# gyro.net
KiCad netlist of a schematic drawn in Altium Designer
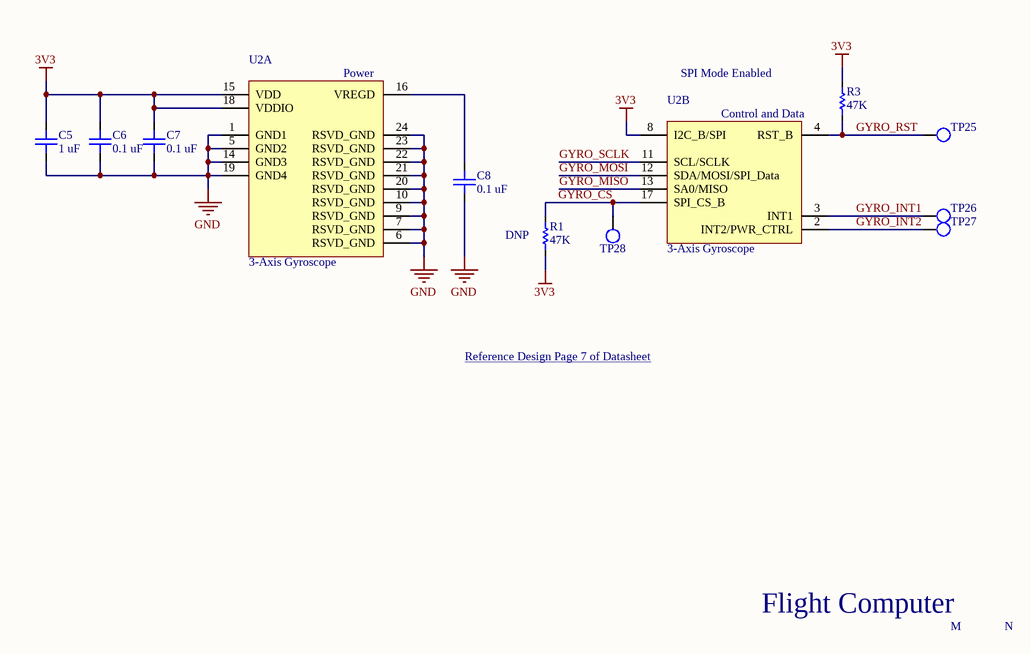
[diagram p0: gyro.SchDoc]

(export (version "E")
  (design (tool "Eeschema 10.0.6"))
  (components
    (comp (ref "C5")
      (value "1 uF")
      (footprint "CAP-CER-0805-TALL")
      (description "10%, 0805")
      (libsource (lib "passive") (part "CAP-CER-1uF-10V"))
    )
    (comp (ref "C6")
      (value "0.1 uF")
      (footprint "CAP-CER-0805-SHORT")
      (description "10%, 0805")
      (libsource (lib "passive") (part "CAP-CER-0.1uF-25V"))
    )
    (comp (ref "C7")
      (value "0.1 uF")
      (footprint "CAP-CER-0805-SHORT")
      (description "10%, 0805")
      (libsource (lib "passive") (part "CAP-CER-0.1uF-25V"))
    )
    (comp (ref "C8")
      (value "0.1 uF")
      (footprint "CAP-CER-0805-SHORT")
      (description "10%, 0805")
      (libsource (lib "passive") (part "CAP-CER-0.1uF-25V"))
    )
    (comp (ref "R1")
      (value "47K")
      (footprint "RES-0805")
      (description "0805")
      (libsource (lib "passive") (part "RES-47K-1/8W"))
    )
    (comp (ref "R3")
      (value "47K")
      (footprint "RES-0805")
      (description "0805")
      (libsource (lib "passive") (part "RES-47K-1/8W"))
    )
    (comp (ref "TP25")
      (value "Test Point")
      (footprint "0603 Test Point")
      (description "0603")
      (libsource (lib "passive") (part "Test Point"))
    )
    (comp (ref "TP26")
      (value "Test Point")
      (footprint "0603 Test Point")
      (description "0603")
      (libsource (lib "passive") (part "Test Point"))
    )
    (comp (ref "TP27")
      (value "Test Point")
      (footprint "0603 Test Point")
      (description "0603")
      (libsource (lib "passive") (part "Test Point"))
    )
    (comp (ref "TP28")
      (value "Test Point")
      (footprint "0603 Test Point")
      (description "0603")
      (libsource (lib "passive") (part "Test Point"))
    )
    (comp (ref "U2")
      (value "3-Axis Gyroscope")
      (footprint "QFN24")
      (description "3-Axis Digital Angular Rate Gyroscope")
      (libsource (lib "ic") (part "FXAS21002C"))
    )
  )
  (nets
    (net (code "1") (name "/GYRO_CS") (class "Default")
      (node (ref "R1") (pin "2") (pinfunction "2_2") (pintype "passive"))
      (node (ref "TP28") (pin "1") (pinfunction "1_1") (pintype "passive"))
      (node (ref "U2") (pin "17") (pinfunction "SPI_CS_B_17") (pintype "passive"))
    )
    (net (code "2") (name "/GYRO_INT1") (class "Default")
      (node (ref "TP26") (pin "1") (pinfunction "1_1") (pintype "passive"))
      (node (ref "U2") (pin "3") (pinfunction "INT1_3") (pintype "passive"))
    )
    (net (code "3") (name "/GYRO_INT2") (class "Default")
      (node (ref "TP27") (pin "1") (pinfunction "1_1") (pintype "passive"))
      (node (ref "U2") (pin "2") (pinfunction "INT2/PWR_CTRL_2") (pintype "passive"))
    )
    (net (code "4") (name "/GYRO_MISO") (class "Default")
      (node (ref "U2") (pin "13") (pinfunction "SA0/MISO_13") (pintype "passive"))
    )
    (net (code "5") (name "/GYRO_MOSI") (class "Default")
      (node (ref "U2") (pin "12") (pinfunction "SDA/MOSI/SPI_Data_12") (pintype "passive"))
    )
    (net (code "6") (name "/GYRO_RST") (class "Default")
      (node (ref "R3") (pin "1") (pinfunction "1_1") (pintype "passive"))
      (node (ref "TP25") (pin "1") (pinfunction "1_1") (pintype "passive"))
      (node (ref "U2") (pin "4") (pinfunction "RST_B_4") (pintype "passive"))
    )
    (net (code "7") (name "/GYRO_SCLK") (class "Default")
      (node (ref "U2") (pin "11") (pinfunction "SCL/SCLK_11") (pintype "passive"))
    )
    (net (code "8") (name "3V3") (class "Default")
      (node (ref "C5") (pin "2") (pinfunction "2_2") (pintype "passive"))
      (node (ref "C6") (pin "2") (pinfunction "2_2") (pintype "passive"))
      (node (ref "C7") (pin "2") (pinfunction "2_2") (pintype "passive"))
      (node (ref "R1") (pin "1") (pinfunction "1_1") (pintype "passive"))
      (node (ref "R3") (pin "2") (pinfunction "2_2") (pintype "passive"))
      (node (ref "U2") (pin "15") (pinfunction "VDD_15") (pintype "passive"))
      (node (ref "U2") (pin "18") (pinfunction "VDDIO_18") (pintype "passive"))
      (node (ref "U2") (pin "8") (pinfunction "I2C_B/SPI_8") (pintype "passive"))
    )
    (net (code "9") (name "GND") (class "Default")
      (node (ref "C5") (pin "1") (pinfunction "1_1") (pintype "passive"))
      (node (ref "C6") (pin "1") (pinfunction "1_1") (pintype "passive"))
      (node (ref "C7") (pin "1") (pinfunction "1_1") (pintype "passive"))
      (node (ref "C8") (pin "1") (pinfunction "1_1") (pintype "passive"))
      (node (ref "U2") (pin "1") (pinfunction "GND1_1") (pintype "passive"))
      (node (ref "U2") (pin "10") (pinfunction "RSVD_GND_10") (pintype "passive"))
      (node (ref "U2") (pin "14") (pinfunction "GND3_14") (pintype "passive"))
      (node (ref "U2") (pin "19") (pinfunction "GND4_19") (pintype "passive"))
      (node (ref "U2") (pin "20") (pinfunction "RSVD_GND_20") (pintype "passive"))
      (node (ref "U2") (pin "21") (pinfunction "RSVD_GND_21") (pintype "passive"))
      (node (ref "U2") (pin "22") (pinfunction "RSVD_GND_22") (pintype "passive"))
      (node (ref "U2") (pin "23") (pinfunction "RSVD_GND_23") (pintype "passive"))
      (node (ref "U2") (pin "24") (pinfunction "RSVD_GND_24") (pintype "passive"))
      (node (ref "U2") (pin "5") (pinfunction "GND2_5") (pintype "passive"))
      (node (ref "U2") (pin "6") (pinfunction "RSVD_GND_6") (pintype "passive"))
      (node (ref "U2") (pin "7") (pinfunction "RSVD_GND_7") (pintype "passive"))
      (node (ref "U2") (pin "9") (pinfunction "RSVD_GND_9") (pintype "passive"))
    )
    (net (code "10") (name "Net-(U2A-VREGD)") (class "Default")
      (node (ref "C8") (pin "2") (pinfunction "2_2") (pintype "passive"))
      (node (ref "U2") (pin "16") (pinfunction "VREGD_16") (pintype "passive"))
    )
  )
)
